# Door.net
KiCad netlist of a schematic drawn in EasyEDA
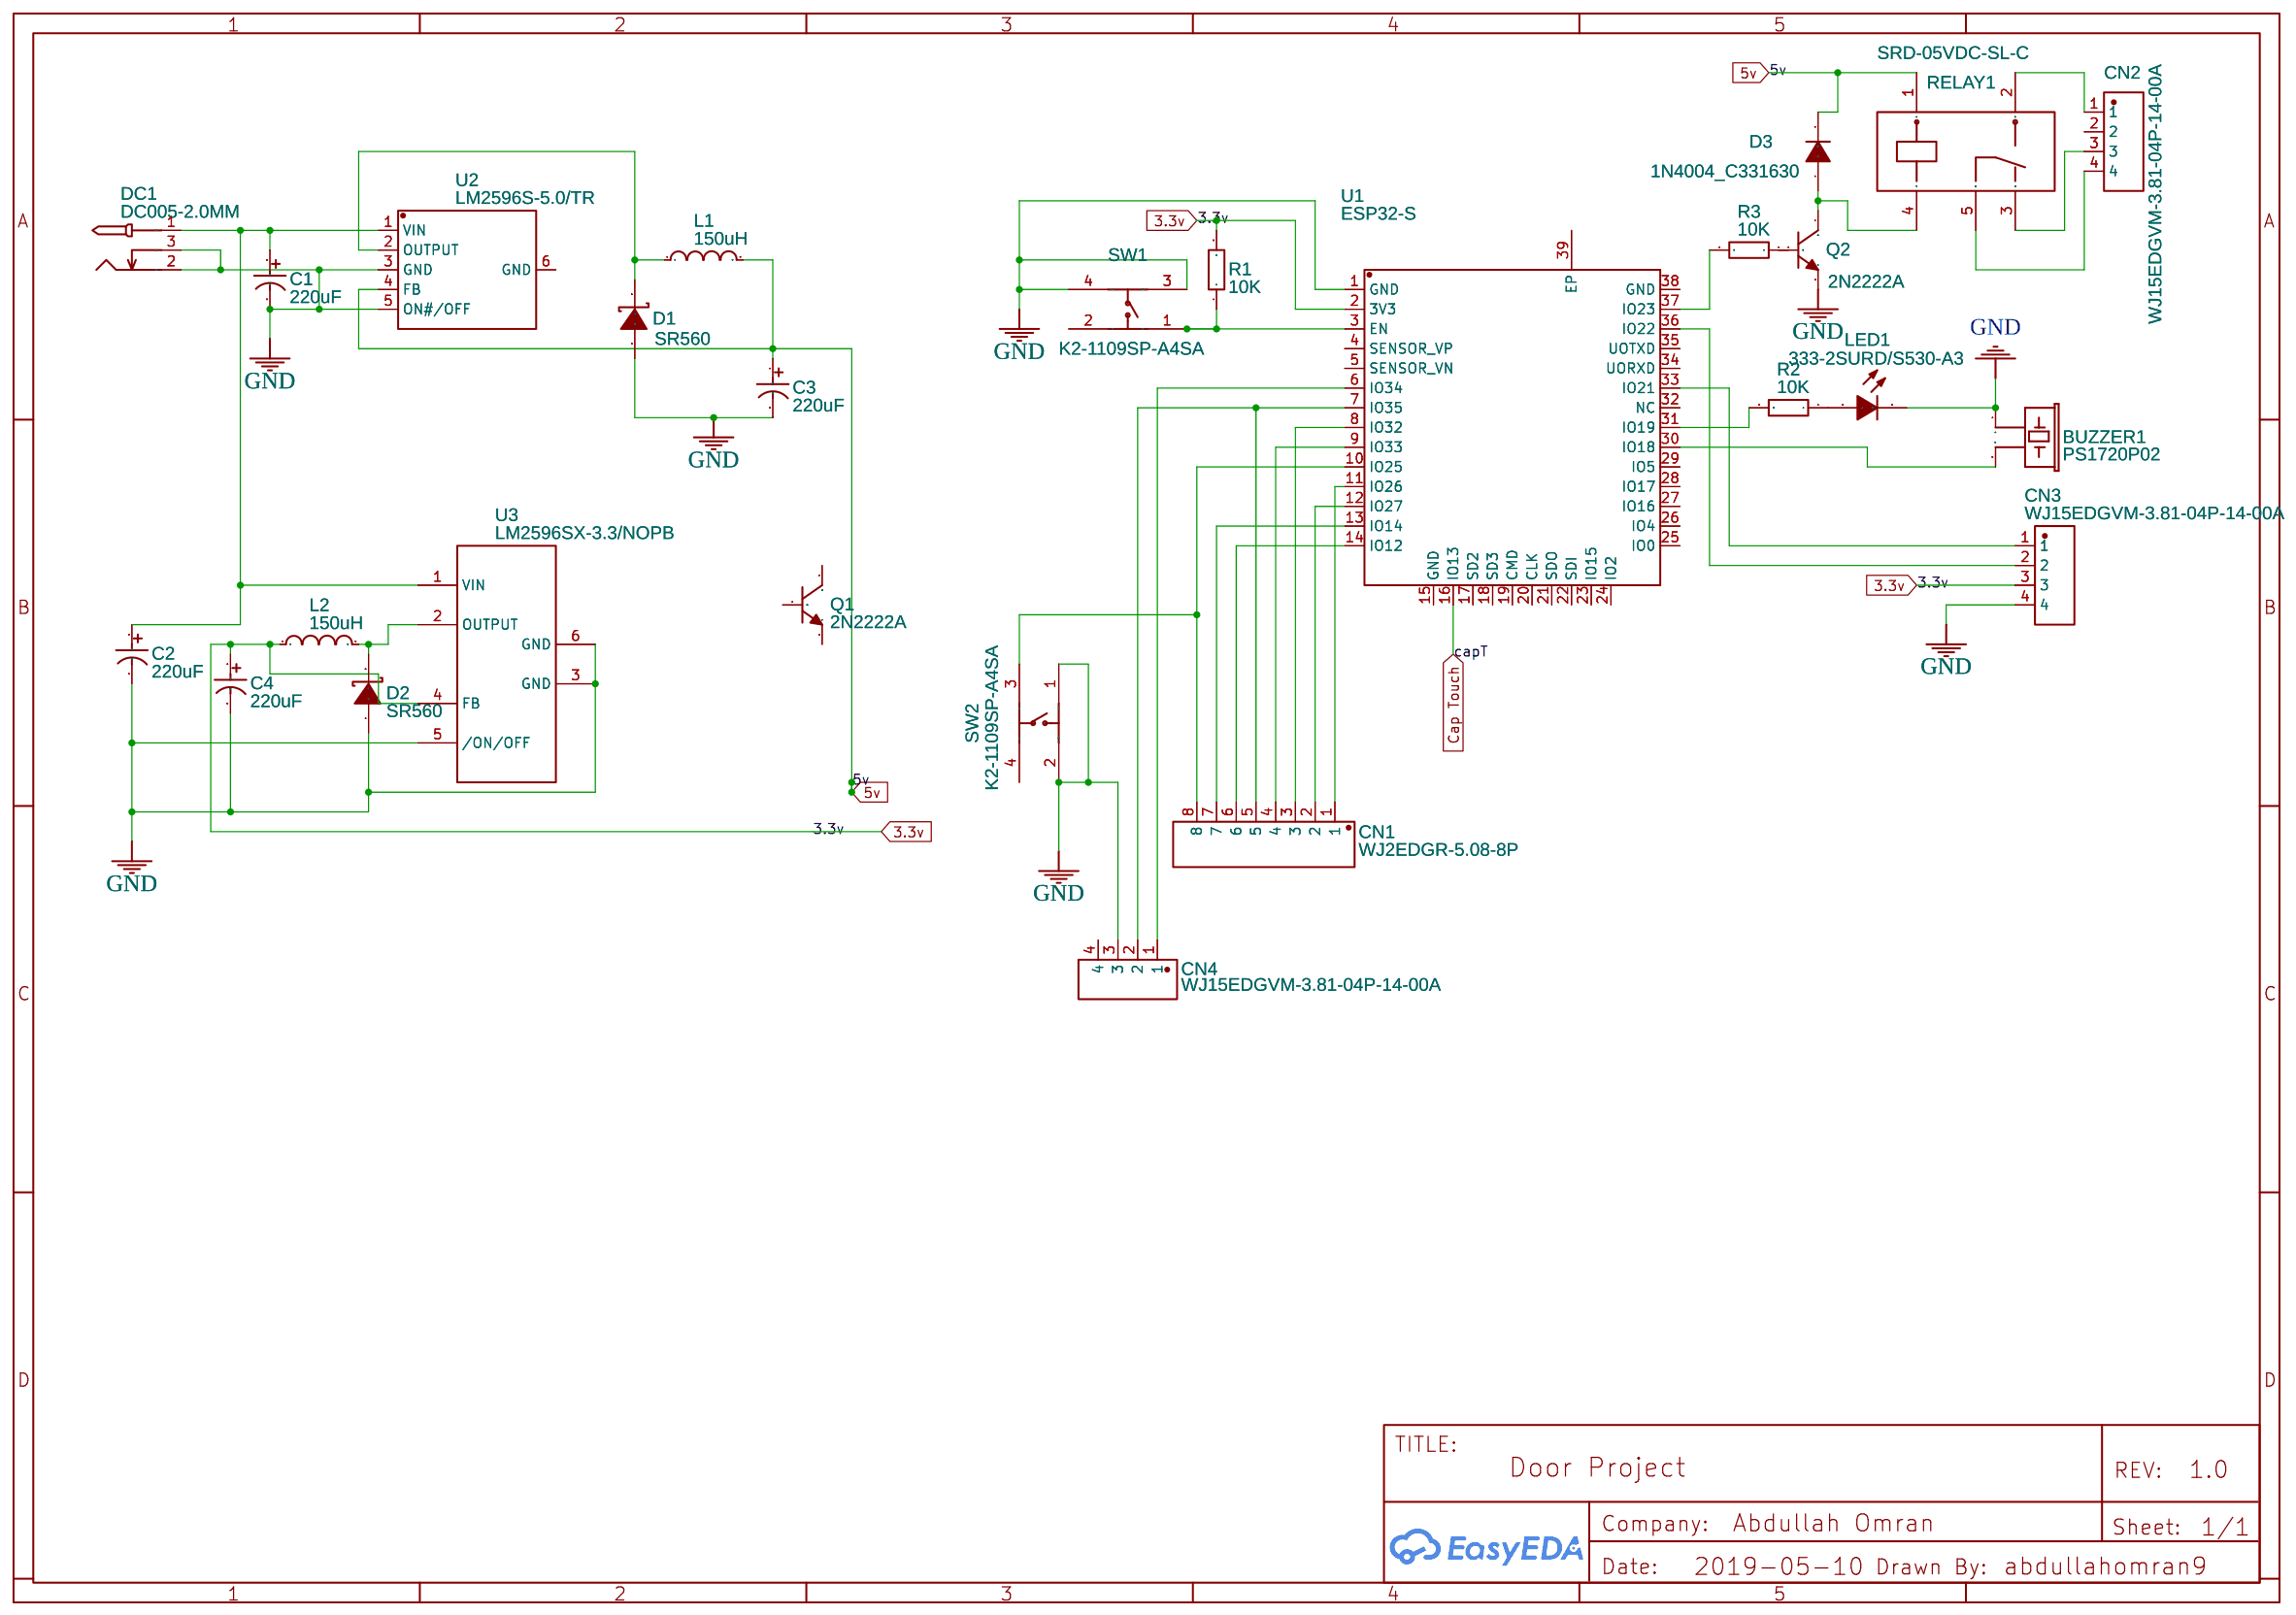
[diagram p0: schematic sheet]

(export (version "E")
  (design (tool "Eeschema 10.0.6"))
  (components
    (comp (ref "BUZZER1")
      (value "PS1720P02")
      (fields (field (name "BOM_Supplier Part") "C96061"))
      (libsource (lib "") (part "Unknown_1020_215"))
    )
    (comp (ref "C1")
      (value "220uF")
      (fields (field (name "BOM_Manufacturer Part") "220uF 25V") (field (name "BOM_Supplier Part") "C12450"))
      (libsource (lib "") (part "220uF 25V"))
    )
    (comp (ref "C2")
      (value "220uF")
      (fields (field (name "BOM_Manufacturer Part") "220uF 25V") (field (name "BOM_Supplier Part") "C12450"))
      (libsource (lib "") (part "220uF 25V"))
    )
    (comp (ref "C3")
      (value "220uF")
      (fields (field (name "BOM_Manufacturer Part") "220uF 25V") (field (name "BOM_Supplier Part") "C12450"))
      (libsource (lib "") (part "220uF 25V"))
    )
    (comp (ref "C4")
      (value "220uF")
      (fields (field (name "BOM_Manufacturer Part") "220uF 25V") (field (name "BOM_Supplier Part") "C12450"))
      (libsource (lib "") (part "220uF 25V"))
    )
    (comp (ref "CN1")
      (value "WJ2EDGR-5.08-8P")
      (fields (field (name "BOM_Supplier Part") "C31423"))
      (libsource (lib "") (part "Unknown_635_415"))
    )
    (comp (ref "CN2")
      (value "WJ15EDGVM-3.81-04P-14-00A")
      (fields (field (name "BOM_Supplier Part") "C157478"))
      (libsource (lib "") (part "Unknown_1065_65"))
    )
    (comp (ref "CN3")
      (value "WJ15EDGVM-3.81-04P-14-00A")
      (fields (field (name "BOM_Supplier Part") "C157478"))
      (libsource (lib "") (part "Unknown_1030_285"))
    )
    (comp (ref "CN4")
      (value "WJ15EDGVM-3.81-04P-14-00A")
      (fields (field (name "BOM_Supplier Part") "C157478"))
      (libsource (lib "") (part "Unknown_565_485"))
    )
    (comp (ref "D1")
      (value "SR560")
      (fields (field (name "BOM_Supplier Part") "C38272"))
      (libsource (lib "") (part "Unknown_315_155"))
    )
    (comp (ref "D2")
      (value "SR560")
      (fields (field (name "BOM_Supplier Part") "C38272"))
      (libsource (lib "") (part "Unknown_180_345"))
    )
    (comp (ref "D3")
      (value "1N4004_C331630")
      (fields (field (name "BOM_Manufacturer Part") "1N4004") (field (name "BOM_Supplier Part") "C331630"))
      (libsource (lib "") (part "Unknown_915_70"))
    )
    (comp (ref "DC1")
      (value "DC005-2.0MM")
      (fields (field (name "BOM_Supplier Part") "C111567"))
      (libsource (lib "") (part "Unknown_65_115"))
    )
    (comp (ref "L1")
      (value "150uH")
      (fields
        (field (name "BOM_Manufacturer Part") "VLU0608-151K")
        (field (name "BOM_Supplier Part") "C128032")
      )
      (libsource (lib "") (part "VLU0608-151K"))
    )
    (comp (ref "L2")
      (value "150uH")
      (fields
        (field (name "BOM_Manufacturer Part") "VLU0608-151K")
        (field (name "BOM_Supplier Part") "C128032")
      )
      (libsource (lib "") (part "VLU0608-151K_1"))
    )
    (comp (ref "LED1")
      (value "333-2SURD/S530-A3")
      (fields (field (name "BOM_Supplier Part") "C87271"))
      (libsource (lib "") (part "Unknown_940_200"))
    )
    (comp (ref "Q1")
      (value "2N2222A")
      (fields (field (name "BOM_Supplier Part") "C358533"))
      (libsource (lib "") (part "Unknown_400_300"))
    )
    (comp (ref "Q2")
      (value "2N2222A")
      (fields (field (name "BOM_Supplier Part") "C358533"))
      (libsource (lib "") (part "Unknown_905_120"))
    )
    (comp (ref "R1")
      (value "10K")
      (fields
        (field (name "BOM_Manufacturer Part") "RD50T5103J")
        (field (name "BOM_Supplier Part") "C167530")
      )
      (libsource (lib "") (part "RD50T5103J_1"))
    )
    (comp (ref "R2")
      (value "10K")
      (fields
        (field (name "BOM_Manufacturer Part") "RD50T5103J")
        (field (name "BOM_Supplier Part") "C167530")
      )
      (libsource (lib "") (part "RD50T5103J"))
    )
    (comp (ref "R3")
      (value "10K")
      (fields
        (field (name "BOM_Manufacturer Part") "RD50T5103J")
        (field (name "BOM_Supplier Part") "C167530")
      )
      (libsource (lib "") (part "RD50T5103J"))
    )
    (comp (ref "RELAY1")
      (value "SRD-05VDC-SL-C")
      (fields (field (name "BOM_Supplier Part") "C35449"))
      (libsource (lib "") (part "Unknown_990_70"))
    )
    (comp (ref "SW1")
      (value "K2-1109SP-A4SA")
      (fields (field (name "BOM_Supplier Part") "C92581"))
      (libsource (lib "") (part "Unknown_565_145"))
    )
    (comp (ref "SW2")
      (value "K2-1109SP-A4SA")
      (fields (field (name "BOM_Supplier Part") "C92581"))
      (libsource (lib "") (part "Unknown_515_360"))
    )
    (comp (ref "U1")
      (value "ESP32-S")
      (fields (field (name "BOM_Supplier Part") "C277944"))
      (libsource (lib "") (part "Unknown_760_230"))
    )
    (comp (ref "U2")
      (value "LM2596S-5.0/TR")
      (fields (field (name "BOM_Supplier Part") "C194349"))
      (libsource (lib "") (part "Unknown_215_130"))
    )
    (comp (ref "U3")
      (value "LM2596SX-3.3/NOPB")
      (fields (field (name "BOM_Supplier Part") "C7929"))
      (libsource (lib "") (part "Unknown_250_330"))
    )
  )
  (nets
    (net (code "1") (name "3.3v") (class "Default")
      (node (ref "C4") (pin "1") (pinfunction "1_1") (pintype "input"))
      (node (ref "CN3") (pin "3") (pinfunction "3_3") (pintype "unspecified"))
      (node (ref "L2") (pin "1") (pinfunction "1_1") (pintype "unspecified"))
      (node (ref "R1") (pin "2") (pinfunction "2_2") (pintype "unspecified"))
      (node (ref "U1") (pin "2") (pinfunction "3V3_2") (pintype "unspecified"))
      (node (ref "U3") (pin "4") (pinfunction "FB_4") (pintype "unspecified"))
    )
    (net (code "2") (name "5v") (class "Default")
      (node (ref "C3") (pin "1") (pinfunction "1_1") (pintype "input"))
      (node (ref "D3") (pin "2") (pinfunction "2_2") (pintype "unspecified"))
      (node (ref "L1") (pin "2") (pinfunction "2_2") (pintype "unspecified"))
      (node (ref "RELAY1") (pin "1") (pinfunction "1_1") (pintype "input"))
      (node (ref "U2") (pin "4") (pinfunction "FB_4") (pintype "unspecified"))
    )
    (net (code "3") (name "Cap Touch") (class "Default")
      (node (ref "U1") (pin "16") (pinfunction "IO13_16") (pintype "unspecified"))
    )
    (net (code "4") (name "GND") (class "Default")
      (node (ref "BUZZER1") (pin "1") (pinfunction "1_1") (pintype "unspecified"))
      (node (ref "C1") (pin "2") (pinfunction "2_2") (pintype "input"))
      (node (ref "C2") (pin "2") (pinfunction "2_2") (pintype "input"))
      (node (ref "C3") (pin "2") (pinfunction "2_2") (pintype "input"))
      (node (ref "C4") (pin "2") (pinfunction "2_2") (pintype "input"))
      (node (ref "CN3") (pin "4") (pinfunction "4_4") (pintype "unspecified"))
      (node (ref "CN4") (pin "3") (pinfunction "3_3") (pintype "unspecified"))
      (node (ref "D1") (pin "1") (pinfunction "A_1") (pintype "unspecified"))
      (node (ref "D2") (pin "1") (pinfunction "A_1") (pintype "unspecified"))
      (node (ref "DC1") (pin "2") (pinfunction "2_2") (pintype "unspecified"))
      (node (ref "DC1") (pin "3") (pinfunction "3_3") (pintype "unspecified"))
      (node (ref "LED1") (pin "2") (pinfunction "C_2") (pintype "input"))
      (node (ref "Q2") (pin "3") (pinfunction "E_3") (pintype "unspecified"))
      (node (ref "SW1") (pin "3") (pinfunction "3_3") (pintype "unspecified"))
      (node (ref "SW1") (pin "4") (pinfunction "4_4") (pintype "unspecified"))
      (node (ref "SW2") (pin "1") (pinfunction "1_1") (pintype "unspecified"))
      (node (ref "SW2") (pin "2") (pinfunction "2_2") (pintype "unspecified"))
      (node (ref "U1") (pin "1") (pinfunction "GND_1") (pintype "unspecified"))
      (node (ref "U2") (pin "3") (pinfunction "GND_3") (pintype "unspecified"))
      (node (ref "U2") (pin "5") (pinfunction "ON#/OFF_5") (pintype "unspecified"))
      (node (ref "U3") (pin "3") (pinfunction "GND_3") (pintype "unspecified"))
      (node (ref "U3") (pin "5") (pinfunction "/ON/OFF_5") (pintype "unspecified"))
      (node (ref "U3") (pin "6") (pinfunction "GND_6") (pintype "unspecified"))
    )
    (net (code "5") (name "Net-(CN2-Pad1)") (class "Default")
      (node (ref "CN2") (pin "1") (pinfunction "1_1") (pintype "unspecified"))
      (node (ref "RELAY1") (pin "2") (pinfunction "2_2") (pintype "input"))
    )
    (net (code "6") (name "Net-(CN2-Pad3)") (class "Default")
      (node (ref "CN2") (pin "3") (pinfunction "3_3") (pintype "unspecified"))
      (node (ref "RELAY1") (pin "3") (pinfunction "3_3") (pintype "input"))
    )
    (net (code "7") (name "Net-(CN2-Pad4)") (class "Default")
      (node (ref "CN2") (pin "4") (pinfunction "4_4") (pintype "unspecified"))
      (node (ref "RELAY1") (pin "5") (pinfunction "5_5") (pintype "input"))
    )
    (net (code "8") (name "Net-(D1-K)") (class "Default")
      (node (ref "D1") (pin "2") (pinfunction "K_2") (pintype "unspecified"))
      (node (ref "L1") (pin "1") (pinfunction "1_1") (pintype "unspecified"))
      (node (ref "U2") (pin "2") (pinfunction "OUTPUT_2") (pintype "unspecified"))
    )
    (net (code "9") (name "Net-(D2-K)") (class "Default")
      (node (ref "D2") (pin "2") (pinfunction "K_2") (pintype "unspecified"))
      (node (ref "L2") (pin "2") (pinfunction "2_2") (pintype "unspecified"))
      (node (ref "U3") (pin "2") (pinfunction "OUTPUT_2") (pintype "unspecified"))
    )
    (net (code "10") (name "Net-(LED1-A)") (class "Default")
      (node (ref "LED1") (pin "1") (pinfunction "A_1") (pintype "input"))
      (node (ref "R2") (pin "1") (pinfunction "1_1") (pintype "unspecified"))
    )
    (net (code "11") (name "Net-(Q2-B)") (class "Default")
      (node (ref "Q2") (pin "2") (pinfunction "B_2") (pintype "unspecified"))
      (node (ref "R3") (pin "1") (pinfunction "1_1") (pintype "unspecified"))
    )
    (net (code "12") (name "Net-(Q2-C)") (class "Default")
      (node (ref "D3") (pin "1") (pinfunction "1_1") (pintype "unspecified"))
      (node (ref "Q2") (pin "1") (pinfunction "C_1") (pintype "unspecified"))
      (node (ref "RELAY1") (pin "4") (pinfunction "4_4") (pintype "input"))
    )
    (net (code "13") (name "Net-(U1-EN)") (class "Default")
      (node (ref "R1") (pin "1") (pinfunction "1_1") (pintype "unspecified"))
      (node (ref "SW1") (pin "1") (pinfunction "1_1") (pintype "unspecified"))
      (node (ref "U1") (pin "3") (pinfunction "EN_3") (pintype "unspecified"))
    )
    (net (code "14") (name "Net-(U1-IO12)") (class "Default")
      (node (ref "CN1") (pin "6") (pinfunction "6_6") (pintype "unspecified"))
      (node (ref "U1") (pin "14") (pinfunction "IO12_14") (pintype "unspecified"))
    )
    (net (code "15") (name "Net-(U1-IO14)") (class "Default")
      (node (ref "CN1") (pin "7") (pinfunction "7_7") (pintype "unspecified"))
      (node (ref "U1") (pin "13") (pinfunction "IO14_13") (pintype "unspecified"))
    )
    (net (code "16") (name "Net-(U1-IO18)") (class "Default")
      (node (ref "BUZZER1") (pin "2") (pinfunction "2_2") (pintype "unspecified"))
      (node (ref "U1") (pin "30") (pinfunction "IO18_30") (pintype "unspecified"))
    )
    (net (code "17") (name "Net-(U1-IO19)") (class "Default")
      (node (ref "R2") (pin "2") (pinfunction "2_2") (pintype "unspecified"))
      (node (ref "U1") (pin "31") (pinfunction "IO19_31") (pintype "unspecified"))
    )
    (net (code "18") (name "Net-(U1-IO21)") (class "Default")
      (node (ref "CN3") (pin "1") (pinfunction "1_1") (pintype "unspecified"))
      (node (ref "U1") (pin "33") (pinfunction "IO21_33") (pintype "unspecified"))
    )
    (net (code "19") (name "Net-(U1-IO22)") (class "Default")
      (node (ref "CN3") (pin "2") (pinfunction "2_2") (pintype "unspecified"))
      (node (ref "U1") (pin "36") (pinfunction "IO22_36") (pintype "unspecified"))
    )
    (net (code "20") (name "Net-(U1-IO23)") (class "Default")
      (node (ref "R3") (pin "2") (pinfunction "2_2") (pintype "unspecified"))
      (node (ref "U1") (pin "37") (pinfunction "IO23_37") (pintype "unspecified"))
    )
    (net (code "21") (name "Net-(U1-IO25)") (class "Default")
      (node (ref "CN1") (pin "8") (pinfunction "8_8") (pintype "unspecified"))
      (node (ref "SW2") (pin "3") (pinfunction "3_3") (pintype "unspecified"))
      (node (ref "U1") (pin "10") (pinfunction "IO25_10") (pintype "unspecified"))
    )
    (net (code "22") (name "Net-(U1-IO26)") (class "Default")
      (node (ref "CN1") (pin "1") (pinfunction "1_1") (pintype "unspecified"))
      (node (ref "U1") (pin "11") (pinfunction "IO26_11") (pintype "unspecified"))
    )
    (net (code "23") (name "Net-(U1-IO27)") (class "Default")
      (node (ref "CN1") (pin "2") (pinfunction "2_2") (pintype "unspecified"))
      (node (ref "U1") (pin "12") (pinfunction "IO27_12") (pintype "unspecified"))
    )
    (net (code "24") (name "Net-(U1-IO32)") (class "Default")
      (node (ref "CN1") (pin "3") (pinfunction "3_3") (pintype "unspecified"))
      (node (ref "U1") (pin "8") (pinfunction "IO32_8") (pintype "unspecified"))
    )
    (net (code "25") (name "Net-(U1-IO33)") (class "Default")
      (node (ref "CN1") (pin "4") (pinfunction "4_4") (pintype "unspecified"))
      (node (ref "U1") (pin "9") (pinfunction "IO33_9") (pintype "unspecified"))
    )
    (net (code "26") (name "Net-(U1-IO34)") (class "Default")
      (node (ref "CN4") (pin "1") (pinfunction "1_1") (pintype "unspecified"))
      (node (ref "U1") (pin "6") (pinfunction "IO34_6") (pintype "unspecified"))
    )
    (net (code "27") (name "Net-(U1-IO35)") (class "Default")
      (node (ref "CN1") (pin "5") (pinfunction "5_5") (pintype "unspecified"))
      (node (ref "CN4") (pin "2") (pinfunction "2_2") (pintype "unspecified"))
      (node (ref "U1") (pin "7") (pinfunction "IO35_7") (pintype "unspecified"))
    )
    (net (code "28") (name "Net-(U2-VIN)") (class "Default")
      (node (ref "C1") (pin "1") (pinfunction "1_1") (pintype "input"))
      (node (ref "C2") (pin "1") (pinfunction "1_1") (pintype "input"))
      (node (ref "DC1") (pin "1") (pinfunction "1_1") (pintype "unspecified"))
      (node (ref "U2") (pin "1") (pinfunction "VIN_1") (pintype "unspecified"))
      (node (ref "U3") (pin "1") (pinfunction "VIN_1") (pintype "unspecified"))
    )
    (net (code "29") (name "unconnected-(CN2-Pad2)") (class "Default")
      (node (ref "CN2") (pin "2") (pinfunction "2_2") (pintype "unspecified"))
    )
    (net (code "30") (name "unconnected-(CN4-Pad4)") (class "Default")
      (node (ref "CN4") (pin "4") (pinfunction "4_4") (pintype "unspecified"))
    )
    (net (code "31") (name "unconnected-(Q1-B-Pad2)") (class "Default")
      (node (ref "Q1") (pin "2") (pinfunction "B_2") (pintype "unspecified"))
    )
    (net (code "32") (name "unconnected-(Q1-C-Pad1)") (class "Default")
      (node (ref "Q1") (pin "1") (pinfunction "C_1") (pintype "unspecified"))
    )
    (net (code "33") (name "unconnected-(Q1-E-Pad3)") (class "Default")
      (node (ref "Q1") (pin "3") (pinfunction "E_3") (pintype "unspecified"))
    )
    (net (code "34") (name "unconnected-(SW1-Pad2)") (class "Default")
      (node (ref "SW1") (pin "2") (pinfunction "2_2") (pintype "unspecified"))
    )
    (net (code "35") (name "unconnected-(SW2-Pad4)") (class "Default")
      (node (ref "SW2") (pin "4") (pinfunction "4_4") (pintype "unspecified"))
    )
    (net (code "36") (name "unconnected-(U1-CLK-Pad20)") (class "Default")
      (node (ref "U1") (pin "20") (pinfunction "CLK_20") (pintype "unspecified"))
    )
    (net (code "37") (name "unconnected-(U1-CMD-Pad19)") (class "Default")
      (node (ref "U1") (pin "19") (pinfunction "CMD_19") (pintype "unspecified"))
    )
    (net (code "38") (name "unconnected-(U1-EP-Pad39)") (class "Default")
      (node (ref "U1") (pin "39") (pinfunction "EP_39") (pintype "unspecified"))
    )
    (net (code "39") (name "unconnected-(U1-GND-Pad15)") (class "Default")
      (node (ref "U1") (pin "15") (pinfunction "GND_15") (pintype "unspecified"))
    )
    (net (code "40") (name "unconnected-(U1-GND-Pad38)") (class "Default")
      (node (ref "U1") (pin "38") (pinfunction "GND_38") (pintype "unspecified"))
    )
    (net (code "41") (name "unconnected-(U1-IO0-Pad25)") (class "Default")
      (node (ref "U1") (pin "25") (pinfunction "IO0_25") (pintype "unspecified"))
    )
    (net (code "42") (name "unconnected-(U1-IO2-Pad24)") (class "Default")
      (node (ref "U1") (pin "24") (pinfunction "IO2_24") (pintype "unspecified"))
    )
    (net (code "43") (name "unconnected-(U1-IO4-Pad26)") (class "Default")
      (node (ref "U1") (pin "26") (pinfunction "IO4_26") (pintype "unspecified"))
    )
    (net (code "44") (name "unconnected-(U1-IO5-Pad29)") (class "Default")
      (node (ref "U1") (pin "29") (pinfunction "IO5_29") (pintype "unspecified"))
    )
    (net (code "45") (name "unconnected-(U1-IO15-Pad23)") (class "Default")
      (node (ref "U1") (pin "23") (pinfunction "IO15_23") (pintype "unspecified"))
    )
    (net (code "46") (name "unconnected-(U1-IO16-Pad27)") (class "Default")
      (node (ref "U1") (pin "27") (pinfunction "IO16_27") (pintype "unspecified"))
    )
    (net (code "47") (name "unconnected-(U1-IO17-Pad28)") (class "Default")
      (node (ref "U1") (pin "28") (pinfunction "IO17_28") (pintype "unspecified"))
    )
    (net (code "48") (name "unconnected-(U1-NC-Pad32)") (class "Default")
      (node (ref "U1") (pin "32") (pinfunction "NC_32") (pintype "unspecified"))
    )
    (net (code "49") (name "unconnected-(U1-SD2-Pad17)") (class "Default")
      (node (ref "U1") (pin "17") (pinfunction "SD2_17") (pintype "unspecified"))
    )
    (net (code "50") (name "unconnected-(U1-SD3-Pad18)") (class "Default")
      (node (ref "U1") (pin "18") (pinfunction "SD3_18") (pintype "unspecified"))
    )
    (net (code "51") (name "unconnected-(U1-SDI-Pad22)") (class "Default")
      (node (ref "U1") (pin "22") (pinfunction "SDI_22") (pintype "unspecified"))
    )
    (net (code "52") (name "unconnected-(U1-SDO-Pad21)") (class "Default")
      (node (ref "U1") (pin "21") (pinfunction "SDO_21") (pintype "unspecified"))
    )
    (net (code "53") (name "unconnected-(U1-SENSOR_VN-Pad5)") (class "Default")
      (node (ref "U1") (pin "5") (pinfunction "SENSOR_VN_5") (pintype "unspecified"))
    )
    (net (code "54") (name "unconnected-(U1-SENSOR_VP-Pad4)") (class "Default")
      (node (ref "U1") (pin "4") (pinfunction "SENSOR_VP_4") (pintype "unspecified"))
    )
    (net (code "55") (name "unconnected-(U1-UORXD-Pad34)") (class "Default")
      (node (ref "U1") (pin "34") (pinfunction "UORXD_34") (pintype "unspecified"))
    )
    (net (code "56") (name "unconnected-(U1-UOTXD-Pad35)") (class "Default")
      (node (ref "U1") (pin "35") (pinfunction "UOTXD_35") (pintype "unspecified"))
    )
    (net (code "57") (name "unconnected-(U2-GND-Pad6)") (class "Default")
      (node (ref "U2") (pin "6") (pinfunction "GND_6") (pintype "unspecified"))
    )
  )
)
